# 1-Schematic_CessnaCitationX_PilotBoard.net
KiCad netlist of a schematic drawn in EasyEDA
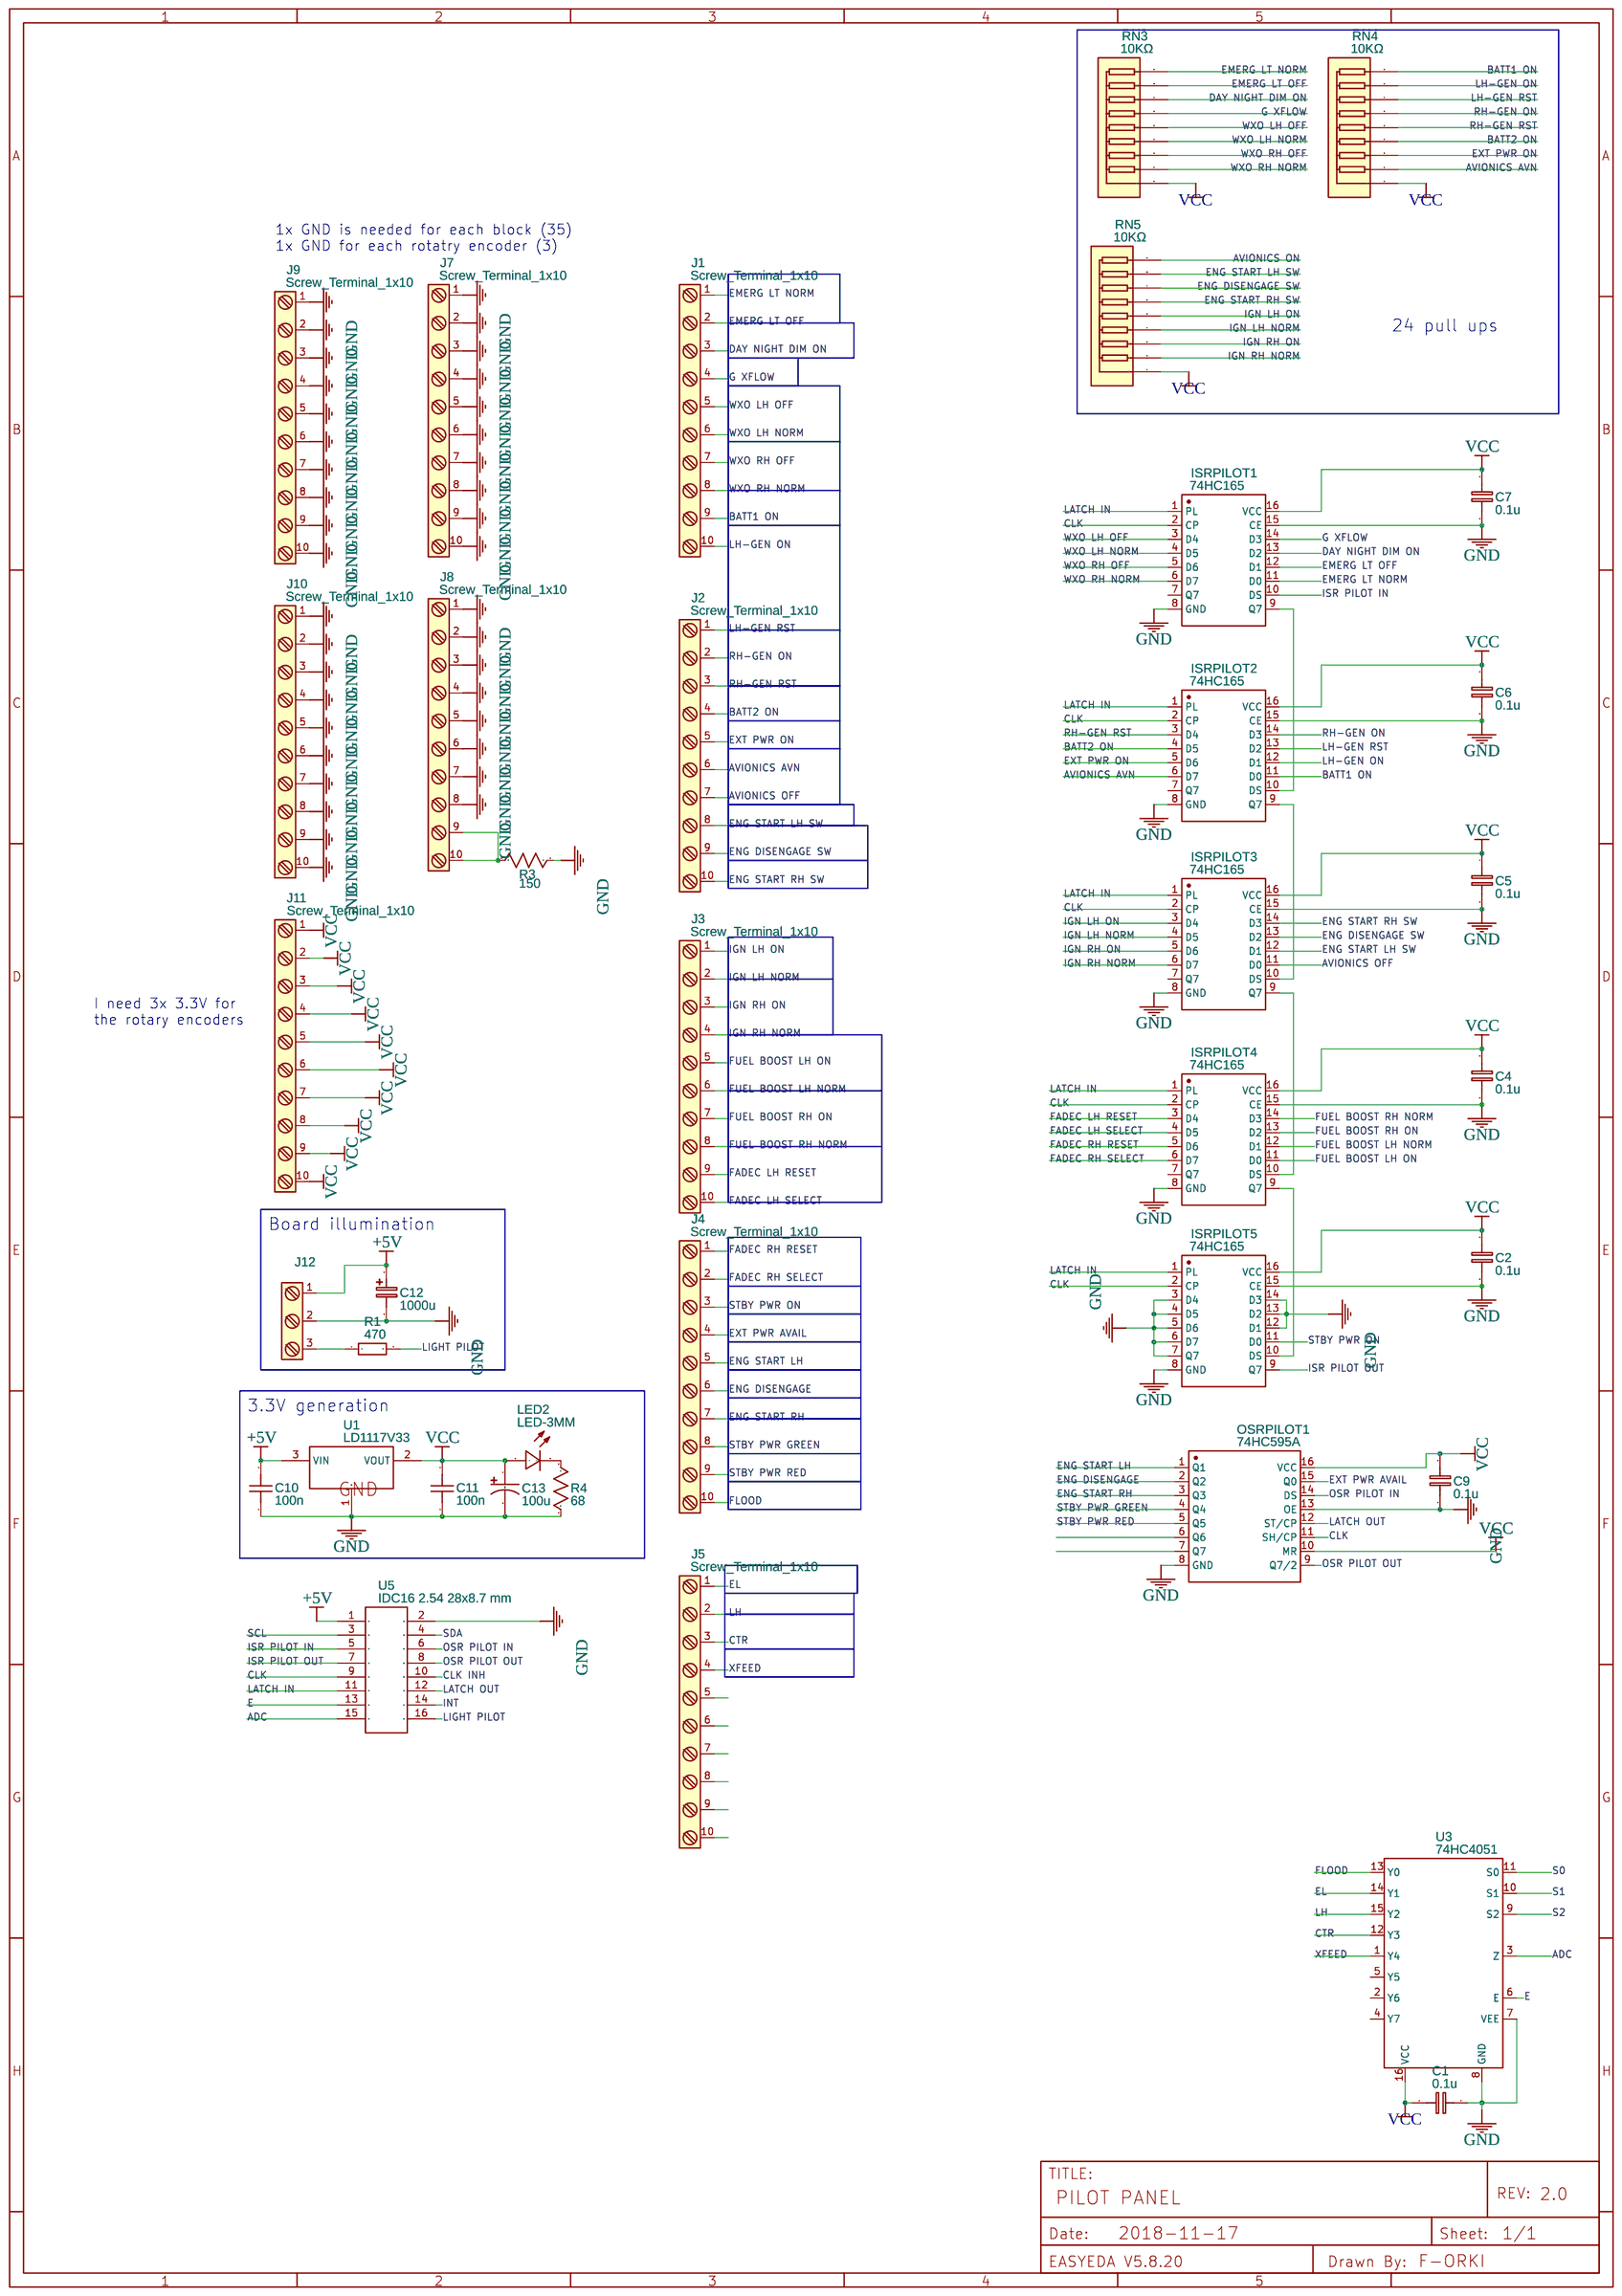
[diagram p0: schematic sheet]

(export (version "E")
  (design (tool "Eeschema 10.0.6"))
  (components
    (comp (ref "C1")
      (value "0.1u")
      (fields (field (name "BOM_Manufacturer Part") "?"))
      (libsource (lib "") (part "Cap_RAD-0.1_EU"))
    )
    (comp (ref "C2")
      (value "0.1u")
      (fields (field (name "BOM_Manufacturer Part") "?"))
      (libsource (lib "") (part "Cap_RAD-0.1_EU_1"))
    )
    (comp (ref "C4")
      (value "0.1u")
      (fields (field (name "BOM_Manufacturer Part") "?"))
      (libsource (lib "") (part "Cap_RAD-0.1_EU_1"))
    )
    (comp (ref "C5")
      (value "0.1u")
      (fields (field (name "BOM_Manufacturer Part") "?"))
      (libsource (lib "") (part "Cap_RAD-0.1_EU_1"))
    )
    (comp (ref "C6")
      (value "0.1u")
      (fields (field (name "BOM_Manufacturer Part") "?"))
      (libsource (lib "") (part "Cap_RAD-0.1_EU_2"))
    )
    (comp (ref "C7")
      (value "0.1u")
      (fields (field (name "BOM_Manufacturer Part") "?"))
      (libsource (lib "") (part "Cap_RAD-0.1_EU_2"))
    )
    (comp (ref "C9")
      (value "0.1u")
      (fields (field (name "BOM_Manufacturer Part") "?"))
      (libsource (lib "") (part "Cap_RAD-0.1_EU_1"))
    )
    (comp (ref "C10")
      (value "100n")
      (fields (field (name "BOM_Manufacturer Part") "?"))
      (libsource (lib "") (part "Cap_RAD-0.1_US"))
    )
    (comp (ref "C11")
      (value "100n")
      (fields (field (name "BOM_Manufacturer Part") "?"))
      (libsource (lib "") (part "Cap_RAD-0.1_US"))
    )
    (comp (ref "C12")
      (value "1000u")
      (fields (field (name "BOM_Manufacturer Part") "?"))
      (libsource (lib "") (part "Cap_Electrolytic(TH)_D3.0XF1.5_EU"))
    )
    (comp (ref "C13")
      (value "100u")
      (fields (field (name "BOM_Manufacturer Part") "?"))
      (libsource (lib "") (part "Cap_Electrolytic(TH)_D3.0XF1.5_US"))
    )
    (comp (ref "ISRPILOT1")
      (value "74HC165")
      (fields
        (field (name "BOM_Manufacturer Part") "74HC165D,653")
        (field (name "BOM_Supplier Part") "C5613")
      )
      (libsource (lib "") (part "Unknown_870_350"))
    )
    (comp (ref "ISRPILOT2")
      (value "74HC165")
      (fields
        (field (name "BOM_Manufacturer Part") "74HC165D,653")
        (field (name "BOM_Supplier Part") "C5613")
      )
      (libsource (lib "") (part "Unknown_870_490"))
    )
    (comp (ref "ISRPILOT3")
      (value "74HC165")
      (fields
        (field (name "BOM_Manufacturer Part") "74HC165D,653")
        (field (name "BOM_Supplier Part") "C5613")
      )
      (libsource (lib "") (part "Unknown_870_625"))
    )
    (comp (ref "ISRPILOT4")
      (value "74HC165")
      (fields
        (field (name "BOM_Manufacturer Part") "74HC165D,653")
        (field (name "BOM_Supplier Part") "C5613")
      )
      (libsource (lib "") (part "Unknown_870_765"))
    )
    (comp (ref "ISRPILOT5")
      (value "74HC165")
      (fields
        (field (name "BOM_Manufacturer Part") "74HC165D,653")
        (field (name "BOM_Supplier Part") "C5613")
      )
      (libsource (lib "") (part "Unknown_870_895"))
    )
    (comp (ref "J1")
      (value "Screw_Terminal_1x10")
      (fields (field (name "BOM_Manufacturer Part") "?"))
      (libsource (lib "") (part "Unknown_495_205"))
    )
    (comp (ref "J2")
      (value "Screw_Terminal_1x10")
      (fields (field (name "BOM_Manufacturer Part") "?"))
      (libsource (lib "") (part "Unknown_495_445"))
    )
    (comp (ref "J3")
      (value "Screw_Terminal_1x10")
      (fields (field (name "BOM_Manufacturer Part") "?"))
      (libsource (lib "") (part "Unknown_495_675"))
    )
    (comp (ref "J4")
      (value "Screw_Terminal_1x10")
      (fields (field (name "BOM_Manufacturer Part") "?"))
      (libsource (lib "") (part "Unknown_495_890"))
    )
    (comp (ref "J5")
      (value "Screw_Terminal_1x10")
      (fields (field (name "BOM_Manufacturer Part") "?"))
      (libsource (lib "") (part "Unknown_495_1130"))
    )
    (comp (ref "J7")
      (value "Screw_Terminal_1x10")
      (fields (field (name "BOM_Manufacturer Part") "?"))
      (libsource (lib "") (part "Unknown_315_205"))
    )
    (comp (ref "J8")
      (value "Screw_Terminal_1x10")
      (fields (field (name "BOM_Manufacturer Part") "?"))
      (libsource (lib "") (part "Unknown_315_430"))
    )
    (comp (ref "J9")
      (value "Screw_Terminal_1x10")
      (fields (field (name "BOM_Manufacturer Part") "?"))
      (libsource (lib "") (part "Unknown_205_210"))
    )
    (comp (ref "J10")
      (value "Screw_Terminal_1x10")
      (fields (field (name "BOM_Manufacturer Part") "?"))
      (libsource (lib "") (part "Unknown_205_435"))
    )
    (comp (ref "J11")
      (value "Screw_Terminal_1x10")
      (fields (field (name "BOM_Manufacturer Part") "?"))
      (libsource (lib "") (part "Unknown_205_750"))
    )
    (comp (ref "J12")
      (value "Screw_Terminal_1x03")
      (fields (field (name "BOM_Manufacturer Part") "?"))
      (libsource (lib "") (part "Unknown_210_940"))
    )
    (comp (ref "LED2")
      (value "LED-3MM")
      (fields
        (field (name "BOM_Manufacturer Part") "204-10SURD/S530-A3")
        (field (name "BOM_Supplier Part") "C99772")
      )
      (libsource (lib "") (part "Unknown_375_1035"))
    )
    (comp (ref "OSRPILOT1")
      (value "74HC595A")
      (fields (field (name "BOM_Supplier Part") "C110383"))
      (libsource (lib "") (part "Unknown_885_1035"))
    )
    (comp (ref "R1")
      (value "470")
      (fields (field (name "BOM_Manufacturer Part") "?"))
      (libsource (lib "") (part "Res_AXIAL-0.3(1/8W)_EU"))
    )
    (comp (ref "R3")
      (value "150")
      (fields (field (name "BOM_Manufacturer Part") "?"))
      (libsource (lib "") (part "Res_AXIAL-0.3(1/8W)_US_1"))
    )
    (comp (ref "R4")
      (value "68")
      (fields (field (name "BOM_Manufacturer Part") "?"))
      (libsource (lib "") (part "Res_AXIAL-0.3(1/8W)_US"))
    )
    (comp (ref "RN3")
      (value "10KΩ")
      (fields (field (name "BOM_Manufacturer Part") "A09-103JP") (field (name "BOM_Supplier Part") "C8692"))
      (libsource (lib "") (part "A09-103JP"))
    )
    (comp (ref "RN4")
      (value "10KΩ")
      (fields (field (name "BOM_Manufacturer Part") "A09-103JP") (field (name "BOM_Supplier Part") "C8692"))
      (libsource (lib "") (part "A09-103JP"))
    )
    (comp (ref "RN5")
      (value "10KΩ")
      (fields (field (name "BOM_Manufacturer Part") "A09-103JP") (field (name "BOM_Supplier Part") "C8692"))
      (libsource (lib "") (part "A09-103JP"))
    )
    (comp (ref "U1")
      (value "LD1117V33")
      (fields (field (name "BOM_Supplier Part") "C283467"))
      (libsource (lib "") (part "Unknown_245_1060"))
    )
    (comp (ref "U3")
      (value "74HC4051")
      (fields (field (name "BOM_Manufacturer Part") "?"))
      (libsource (lib "") (part "Unknown_1030_1395"))
    )
    (comp (ref "U5")
      (value "IDC16 2.54 28x8.7 mm")
      (fields (field (name "BOM_Manufacturer Part") "?"))
      (libsource (lib "") (part "Unknown_235_1235"))
    )
  )
  (nets
    (net (code "1") (name "+5V") (class "Default")
      (node (ref "C10") (pin "2") (pinfunction "2_2") (pintype "unspecified"))
      (node (ref "C12") (pin "1") (pinfunction "1_1") (pintype "unspecified"))
      (node (ref "J12") (pin "1") (pintype "unspecified"))
      (node (ref "U1") (pin "3") (pinfunction "VIN_3") (pintype "passive"))
      (node (ref "U5") (pin "1") (pinfunction "P1_1") (pintype "unspecified"))
    )
    (net (code "2") (name "/ADC") (class "Default")
      (node (ref "U3") (pin "3") (pinfunction "Z_3") (pintype "unspecified"))
      (node (ref "U5") (pin "15") (pinfunction "15_15") (pintype "unspecified"))
    )
    (net (code "3") (name "/AVIONICS AVN") (class "Default")
      (node (ref "ISRPILOT2") (pin "6") (pinfunction "D7_6") (pintype "unspecified"))
      (node (ref "J2") (pin "6") (pintype "unspecified"))
      (node (ref "RN4") (pin "2") (pinfunction "2_2") (pintype "input"))
    )
    (net (code "4") (name "/AVIONICS OFF") (class "Default")
      (node (ref "ISRPILOT3") (pin "11") (pinfunction "D0_11") (pintype "unspecified"))
      (node (ref "J2") (pin "7") (pintype "unspecified"))
    )
    (net (code "5") (name "/AVIONICS ON") (class "Default")
      (node (ref "RN5") (pin "9") (pinfunction "9_9") (pintype "input"))
    )
    (net (code "6") (name "/BATT1 ON") (class "Default")
      (node (ref "ISRPILOT2") (pin "11") (pinfunction "D0_11") (pintype "unspecified"))
      (node (ref "J1") (pin "9") (pintype "unspecified"))
      (node (ref "RN4") (pin "9") (pinfunction "9_9") (pintype "input"))
    )
    (net (code "7") (name "/BATT2 ON") (class "Default")
      (node (ref "ISRPILOT2") (pin "4") (pinfunction "D5_4") (pintype "unspecified"))
      (node (ref "J2") (pin "4") (pintype "unspecified"))
      (node (ref "RN4") (pin "4") (pinfunction "4_4") (pintype "input"))
    )
    (net (code "8") (name "/CLK") (class "Default")
      (node (ref "ISRPILOT1") (pin "2") (pinfunction "CP_2") (pintype "unspecified"))
      (node (ref "ISRPILOT2") (pin "2") (pinfunction "CP_2") (pintype "unspecified"))
      (node (ref "ISRPILOT3") (pin "2") (pinfunction "CP_2") (pintype "unspecified"))
      (node (ref "ISRPILOT4") (pin "2") (pinfunction "CP_2") (pintype "unspecified"))
      (node (ref "ISRPILOT5") (pin "2") (pinfunction "CP_2") (pintype "unspecified"))
      (node (ref "OSRPILOT1") (pin "11") (pinfunction "SH/CP_11") (pintype "unspecified"))
      (node (ref "U5") (pin "9") (pinfunction "P9_9") (pintype "unspecified"))
    )
    (net (code "9") (name "/CLK INH") (class "Default")
      (node (ref "U5") (pin "10") (pinfunction "P10_10") (pintype "unspecified"))
    )
    (net (code "10") (name "/CTR") (class "Default")
      (node (ref "J5") (pin "3") (pintype "unspecified"))
      (node (ref "U3") (pin "12") (pinfunction "Y3_12") (pintype "unspecified"))
    )
    (net (code "11") (name "/DAY NIGHT DIM ON") (class "Default")
      (node (ref "ISRPILOT1") (pin "13") (pinfunction "D2_13") (pintype "unspecified"))
      (node (ref "J1") (pin "3") (pintype "unspecified"))
      (node (ref "RN3") (pin "7") (pinfunction "7_7") (pintype "input"))
    )
    (net (code "12") (name "/E") (class "Default")
      (node (ref "U3") (pin "6") (pinfunction "E_6") (pintype "unspecified"))
      (node (ref "U5") (pin "13") (pinfunction "13_13") (pintype "unspecified"))
    )
    (net (code "13") (name "/EL") (class "Default")
      (node (ref "J5") (pin "1") (pintype "unspecified"))
      (node (ref "U3") (pin "14") (pinfunction "Y1_14") (pintype "unspecified"))
    )
    (net (code "14") (name "/EMERG LT NORM") (class "Default")
      (node (ref "ISRPILOT1") (pin "11") (pinfunction "D0_11") (pintype "unspecified"))
      (node (ref "J1") (pin "1") (pintype "unspecified"))
      (node (ref "RN3") (pin "9") (pinfunction "9_9") (pintype "input"))
    )
    (net (code "15") (name "/EMERG LT OFF") (class "Default")
      (node (ref "ISRPILOT1") (pin "12") (pinfunction "D1_12") (pintype "unspecified"))
      (node (ref "J1") (pin "2") (pintype "unspecified"))
      (node (ref "RN3") (pin "8") (pinfunction "8_8") (pintype "input"))
    )
    (net (code "16") (name "/ENG DISENGAGE") (class "Default")
      (node (ref "J4") (pin "6") (pintype "unspecified"))
      (node (ref "OSRPILOT1") (pin "2") (pinfunction "Q2_2") (pintype "unspecified"))
    )
    (net (code "17") (name "/ENG DISENGAGE SW") (class "Default")
      (node (ref "ISRPILOT3") (pin "13") (pinfunction "D2_13") (pintype "unspecified"))
      (node (ref "J2") (pin "9") (pintype "unspecified"))
      (node (ref "RN5") (pin "7") (pinfunction "7_7") (pintype "input"))
    )
    (net (code "18") (name "/ENG START LH") (class "Default")
      (node (ref "J4") (pin "5") (pintype "unspecified"))
      (node (ref "OSRPILOT1") (pin "1") (pinfunction "Q1_1") (pintype "unspecified"))
    )
    (net (code "19") (name "/ENG START LH SW") (class "Default")
      (node (ref "ISRPILOT3") (pin "12") (pinfunction "D1_12") (pintype "unspecified"))
      (node (ref "J2") (pin "8") (pintype "unspecified"))
      (node (ref "RN5") (pin "8") (pinfunction "8_8") (pintype "input"))
    )
    (net (code "20") (name "/ENG START RH") (class "Default")
      (node (ref "J4") (pin "7") (pintype "unspecified"))
      (node (ref "OSRPILOT1") (pin "3") (pinfunction "Q3_3") (pintype "unspecified"))
    )
    (net (code "21") (name "/ENG START RH SW") (class "Default")
      (node (ref "ISRPILOT3") (pin "14") (pinfunction "D3_14") (pintype "unspecified"))
      (node (ref "J2") (pin "10") (pintype "unspecified"))
      (node (ref "RN5") (pin "6") (pinfunction "6_6") (pintype "input"))
    )
    (net (code "22") (name "/EXT PWR AVAIL") (class "Default")
      (node (ref "J4") (pin "4") (pintype "unspecified"))
      (node (ref "OSRPILOT1") (pin "15") (pinfunction "Q0_15") (pintype "unspecified"))
    )
    (net (code "23") (name "/EXT PWR ON") (class "Default")
      (node (ref "ISRPILOT2") (pin "5") (pinfunction "D6_5") (pintype "unspecified"))
      (node (ref "J2") (pin "5") (pintype "unspecified"))
      (node (ref "RN4") (pin "3") (pinfunction "3_3") (pintype "input"))
    )
    (net (code "24") (name "/FADEC LH RESET") (class "Default")
      (node (ref "ISRPILOT4") (pin "3") (pinfunction "D4_3") (pintype "unspecified"))
      (node (ref "J3") (pin "9") (pintype "unspecified"))
    )
    (net (code "25") (name "/FADEC LH SELECT") (class "Default")
      (node (ref "ISRPILOT4") (pin "4") (pinfunction "D5_4") (pintype "unspecified"))
      (node (ref "J3") (pin "10") (pintype "unspecified"))
    )
    (net (code "26") (name "/FADEC RH RESET") (class "Default")
      (node (ref "ISRPILOT4") (pin "5") (pinfunction "D6_5") (pintype "unspecified"))
      (node (ref "J4") (pin "1") (pintype "unspecified"))
    )
    (net (code "27") (name "/FADEC RH SELECT") (class "Default")
      (node (ref "ISRPILOT4") (pin "6") (pinfunction "D7_6") (pintype "unspecified"))
      (node (ref "J4") (pin "2") (pintype "unspecified"))
    )
    (net (code "28") (name "/FLOOD") (class "Default")
      (node (ref "J4") (pin "10") (pintype "unspecified"))
      (node (ref "U3") (pin "13") (pinfunction "Y0_13") (pintype "unspecified"))
    )
    (net (code "29") (name "/FUEL BOOST LH NORM") (class "Default")
      (node (ref "ISRPILOT4") (pin "12") (pinfunction "D1_12") (pintype "unspecified"))
      (node (ref "J3") (pin "6") (pintype "unspecified"))
    )
    (net (code "30") (name "/FUEL BOOST LH ON") (class "Default")
      (node (ref "ISRPILOT4") (pin "11") (pinfunction "D0_11") (pintype "unspecified"))
      (node (ref "J3") (pin "5") (pintype "unspecified"))
    )
    (net (code "31") (name "/FUEL BOOST RH NORM") (class "Default")
      (node (ref "ISRPILOT4") (pin "14") (pinfunction "D3_14") (pintype "unspecified"))
      (node (ref "J3") (pin "8") (pintype "unspecified"))
    )
    (net (code "32") (name "/FUEL BOOST RH ON") (class "Default")
      (node (ref "ISRPILOT4") (pin "13") (pinfunction "D2_13") (pintype "unspecified"))
      (node (ref "J3") (pin "7") (pintype "unspecified"))
    )
    (net (code "33") (name "/G XFLOW") (class "Default")
      (node (ref "ISRPILOT1") (pin "14") (pinfunction "D3_14") (pintype "unspecified"))
      (node (ref "J1") (pin "4") (pintype "unspecified"))
      (node (ref "RN3") (pin "6") (pinfunction "6_6") (pintype "input"))
    )
    (net (code "34") (name "/IGN LH NORM") (class "Default")
      (node (ref "ISRPILOT3") (pin "4") (pinfunction "D5_4") (pintype "unspecified"))
      (node (ref "J3") (pin "2") (pintype "unspecified"))
      (node (ref "RN5") (pin "4") (pinfunction "4_4") (pintype "input"))
    )
    (net (code "35") (name "/IGN LH ON") (class "Default")
      (node (ref "ISRPILOT3") (pin "3") (pinfunction "D4_3") (pintype "unspecified"))
      (node (ref "J3") (pin "1") (pintype "unspecified"))
      (node (ref "RN5") (pin "5") (pinfunction "5_5") (pintype "input"))
    )
    (net (code "36") (name "/IGN RH NORM") (class "Default")
      (node (ref "ISRPILOT3") (pin "6") (pinfunction "D7_6") (pintype "unspecified"))
      (node (ref "J3") (pin "4") (pintype "unspecified"))
      (node (ref "RN5") (pin "2") (pinfunction "2_2") (pintype "input"))
    )
    (net (code "37") (name "/IGN RH ON") (class "Default")
      (node (ref "ISRPILOT3") (pin "5") (pinfunction "D6_5") (pintype "unspecified"))
      (node (ref "J3") (pin "3") (pintype "unspecified"))
      (node (ref "RN5") (pin "3") (pinfunction "3_3") (pintype "input"))
    )
    (net (code "38") (name "/INT") (class "Default")
      (node (ref "U5") (pin "14") (pinfunction "14_14") (pintype "unspecified"))
    )
    (net (code "39") (name "/ISR PILOT IN") (class "Default")
      (node (ref "ISRPILOT1") (pin "10") (pinfunction "DS_10") (pintype "unspecified"))
      (node (ref "U5") (pin "5") (pinfunction "P5_5") (pintype "unspecified"))
    )
    (net (code "40") (name "/ISR PILOT OUT") (class "Default")
      (node (ref "ISRPILOT5") (pin "9") (pinfunction "Q7_9") (pintype "unspecified"))
      (node (ref "U5") (pin "7") (pinfunction "P7_7") (pintype "unspecified"))
    )
    (net (code "41") (name "/LATCH IN") (class "Default")
      (node (ref "ISRPILOT1") (pin "1") (pinfunction "PL_1") (pintype "unspecified"))
      (node (ref "ISRPILOT2") (pin "1") (pinfunction "PL_1") (pintype "unspecified"))
      (node (ref "ISRPILOT3") (pin "1") (pinfunction "PL_1") (pintype "unspecified"))
      (node (ref "ISRPILOT4") (pin "1") (pinfunction "PL_1") (pintype "unspecified"))
      (node (ref "ISRPILOT5") (pin "1") (pinfunction "PL_1") (pintype "unspecified"))
      (node (ref "U5") (pin "11") (pinfunction "11_11") (pintype "unspecified"))
    )
    (net (code "42") (name "/LATCH OUT") (class "Default")
      (node (ref "OSRPILOT1") (pin "12") (pinfunction "ST/CP_12") (pintype "unspecified"))
      (node (ref "U5") (pin "12") (pinfunction "12_12") (pintype "unspecified"))
    )
    (net (code "43") (name "/LH") (class "Default")
      (node (ref "J5") (pin "2") (pintype "unspecified"))
      (node (ref "U3") (pin "15") (pinfunction "Y2_15") (pintype "unspecified"))
    )
    (net (code "44") (name "/LH-GEN ON") (class "Default")
      (node (ref "ISRPILOT2") (pin "12") (pinfunction "D1_12") (pintype "unspecified"))
      (node (ref "J1") (pin "10") (pintype "unspecified"))
      (node (ref "RN4") (pin "8") (pinfunction "8_8") (pintype "input"))
    )
    (net (code "45") (name "/LH-GEN RST") (class "Default")
      (node (ref "ISRPILOT2") (pin "13") (pinfunction "D2_13") (pintype "unspecified"))
      (node (ref "J2") (pin "1") (pintype "unspecified"))
      (node (ref "RN4") (pin "7") (pinfunction "7_7") (pintype "input"))
    )
    (net (code "46") (name "/LIGHT PILOT") (class "Default")
      (node (ref "R1") (pin "2") (pinfunction "2_2") (pintype "unspecified"))
      (node (ref "U5") (pin "16") (pinfunction "16_16") (pintype "unspecified"))
    )
    (net (code "47") (name "/OSR PILOT IN") (class "Default")
      (node (ref "OSRPILOT1") (pin "14") (pinfunction "DS_14") (pintype "unspecified"))
      (node (ref "U5") (pin "6") (pinfunction "P6_6") (pintype "unspecified"))
    )
    (net (code "48") (name "/OSR PILOT OUT") (class "Default")
      (node (ref "OSRPILOT1") (pin "9") (pinfunction "Q7/2_9") (pintype "unspecified"))
      (node (ref "U5") (pin "8") (pinfunction "P8_8") (pintype "unspecified"))
    )
    (net (code "49") (name "/RH-GEN ON") (class "Default")
      (node (ref "ISRPILOT2") (pin "14") (pinfunction "D3_14") (pintype "unspecified"))
      (node (ref "J2") (pin "2") (pintype "unspecified"))
      (node (ref "RN4") (pin "6") (pinfunction "6_6") (pintype "input"))
    )
    (net (code "50") (name "/RH-GEN RST") (class "Default")
      (node (ref "ISRPILOT2") (pin "3") (pinfunction "D4_3") (pintype "unspecified"))
      (node (ref "J2") (pin "3") (pintype "unspecified"))
      (node (ref "RN4") (pin "5") (pinfunction "5_5") (pintype "input"))
    )
    (net (code "51") (name "/S0") (class "Default")
      (node (ref "U3") (pin "11") (pinfunction "S0_11") (pintype "unspecified"))
    )
    (net (code "52") (name "/S1") (class "Default")
      (node (ref "U3") (pin "10") (pinfunction "S1_10") (pintype "unspecified"))
    )
    (net (code "53") (name "/S2") (class "Default")
      (node (ref "U3") (pin "9") (pinfunction "S2_9") (pintype "unspecified"))
    )
    (net (code "54") (name "/SCL") (class "Default")
      (node (ref "U5") (pin "3") (pinfunction "P3_3") (pintype "unspecified"))
    )
    (net (code "55") (name "/SDA") (class "Default")
      (node (ref "U5") (pin "4") (pinfunction "P4_4") (pintype "unspecified"))
    )
    (net (code "56") (name "/STBY PWR GREEN") (class "Default")
      (node (ref "J4") (pin "8") (pintype "unspecified"))
      (node (ref "OSRPILOT1") (pin "4") (pinfunction "Q4_4") (pintype "unspecified"))
    )
    (net (code "57") (name "/STBY PWR ON") (class "Default")
      (node (ref "ISRPILOT5") (pin "11") (pinfunction "D0_11") (pintype "unspecified"))
      (node (ref "J4") (pin "3") (pintype "unspecified"))
    )
    (net (code "58") (name "/STBY PWR RED") (class "Default")
      (node (ref "J4") (pin "9") (pintype "unspecified"))
      (node (ref "OSRPILOT1") (pin "5") (pinfunction "Q5_5") (pintype "unspecified"))
    )
    (net (code "59") (name "/WXO LH NORM") (class "Default")
      (node (ref "ISRPILOT1") (pin "4") (pinfunction "D5_4") (pintype "unspecified"))
      (node (ref "J1") (pin "6") (pintype "unspecified"))
      (node (ref "RN3") (pin "4") (pinfunction "4_4") (pintype "input"))
    )
    (net (code "60") (name "/WXO LH OFF") (class "Default")
      (node (ref "ISRPILOT1") (pin "3") (pinfunction "D4_3") (pintype "unspecified"))
      (node (ref "J1") (pin "5") (pintype "unspecified"))
      (node (ref "RN3") (pin "5") (pinfunction "5_5") (pintype "input"))
    )
    (net (code "61") (name "/WXO RH NORM") (class "Default")
      (node (ref "ISRPILOT1") (pin "6") (pinfunction "D7_6") (pintype "unspecified"))
      (node (ref "J1") (pin "8") (pintype "unspecified"))
      (node (ref "RN3") (pin "2") (pinfunction "2_2") (pintype "input"))
    )
    (net (code "62") (name "/WXO RH OFF") (class "Default")
      (node (ref "ISRPILOT1") (pin "5") (pinfunction "D6_5") (pintype "unspecified"))
      (node (ref "J1") (pin "7") (pintype "unspecified"))
      (node (ref "RN3") (pin "3") (pinfunction "3_3") (pintype "input"))
    )
    (net (code "63") (name "/XFEED") (class "Default")
      (node (ref "J5") (pin "4") (pintype "unspecified"))
      (node (ref "U3") (pin "1") (pinfunction "Y4_1") (pintype "unspecified"))
    )
    (net (code "64") (name "GND") (class "Default")
      (node (ref "C1") (pin "1") (pinfunction "1_1") (pintype "unspecified"))
      (node (ref "C10") (pin "1") (pinfunction "1_1") (pintype "unspecified"))
      (node (ref "C11") (pin "1") (pinfunction "1_1") (pintype "unspecified"))
      (node (ref "C12") (pin "2") (pinfunction "2_2") (pintype "unspecified"))
      (node (ref "C13") (pin "2") (pinfunction "2_2") (pintype "unspecified"))
      (node (ref "C2") (pin "2") (pinfunction "2_2") (pintype "unspecified"))
      (node (ref "C4") (pin "2") (pinfunction "2_2") (pintype "unspecified"))
      (node (ref "C5") (pin "2") (pinfunction "2_2") (pintype "unspecified"))
      (node (ref "C6") (pin "2") (pinfunction "2_2") (pintype "unspecified"))
      (node (ref "C7") (pin "2") (pinfunction "2_2") (pintype "unspecified"))
      (node (ref "C9") (pin "2") (pinfunction "2_2") (pintype "unspecified"))
      (node (ref "ISRPILOT1") (pin "15") (pinfunction "CE_15") (pintype "unspecified"))
      (node (ref "ISRPILOT1") (pin "8") (pinfunction "GND_8") (pintype "unspecified"))
      (node (ref "ISRPILOT2") (pin "15") (pinfunction "CE_15") (pintype "unspecified"))
      (node (ref "ISRPILOT2") (pin "8") (pinfunction "GND_8") (pintype "unspecified"))
      (node (ref "ISRPILOT3") (pin "15") (pinfunction "CE_15") (pintype "unspecified"))
      (node (ref "ISRPILOT3") (pin "8") (pinfunction "GND_8") (pintype "unspecified"))
      (node (ref "ISRPILOT4") (pin "15") (pinfunction "CE_15") (pintype "unspecified"))
      (node (ref "ISRPILOT4") (pin "8") (pinfunction "GND_8") (pintype "unspecified"))
      (node (ref "ISRPILOT5") (pin "12") (pinfunction "D1_12") (pintype "unspecified"))
      (node (ref "ISRPILOT5") (pin "13") (pinfunction "D2_13") (pintype "unspecified"))
      (node (ref "ISRPILOT5") (pin "14") (pinfunction "D3_14") (pintype "unspecified"))
      (node (ref "ISRPILOT5") (pin "15") (pinfunction "CE_15") (pintype "unspecified"))
      (node (ref "ISRPILOT5") (pin "3") (pinfunction "D4_3") (pintype "unspecified"))
      (node (ref "ISRPILOT5") (pin "4") (pinfunction "D5_4") (pintype "unspecified"))
      (node (ref "ISRPILOT5") (pin "5") (pinfunction "D6_5") (pintype "unspecified"))
      (node (ref "ISRPILOT5") (pin "6") (pinfunction "D7_6") (pintype "unspecified"))
      (node (ref "ISRPILOT5") (pin "7") (pinfunction "Q7_7") (pintype "unspecified"))
      (node (ref "ISRPILOT5") (pin "8") (pinfunction "GND_8") (pintype "unspecified"))
      (node (ref "J10") (pin "1") (pintype "unspecified"))
      (node (ref "J10") (pin "10") (pintype "unspecified"))
      (node (ref "J10") (pin "2") (pintype "unspecified"))
      (node (ref "J10") (pin "3") (pintype "unspecified"))
      (node (ref "J10") (pin "4") (pintype "unspecified"))
      (node (ref "J10") (pin "5") (pintype "unspecified"))
      (node (ref "J10") (pin "6") (pintype "unspecified"))
      (node (ref "J10") (pin "7") (pintype "unspecified"))
      (node (ref "J10") (pin "8") (pintype "unspecified"))
      (node (ref "J10") (pin "9") (pintype "unspecified"))
      (node (ref "J12") (pin "2") (pintype "unspecified"))
      (node (ref "J7") (pin "1") (pintype "unspecified"))
      (node (ref "J7") (pin "10") (pintype "unspecified"))
      (node (ref "J7") (pin "2") (pintype "unspecified"))
      (node (ref "J7") (pin "3") (pintype "unspecified"))
      (node (ref "J7") (pin "4") (pintype "unspecified"))
      (node (ref "J7") (pin "5") (pintype "unspecified"))
      (node (ref "J7") (pin "6") (pintype "unspecified"))
      (node (ref "J7") (pin "7") (pintype "unspecified"))
      (node (ref "J7") (pin "8") (pintype "unspecified"))
      (node (ref "J7") (pin "9") (pintype "unspecified"))
      (node (ref "J8") (pin "1") (pintype "unspecified"))
      (node (ref "J8") (pin "2") (pintype "unspecified"))
      (node (ref "J8") (pin "3") (pintype "unspecified"))
      (node (ref "J8") (pin "4") (pintype "unspecified"))
      (node (ref "J8") (pin "5") (pintype "unspecified"))
      (node (ref "J8") (pin "6") (pintype "unspecified"))
      (node (ref "J8") (pin "7") (pintype "unspecified"))
      (node (ref "J8") (pin "8") (pintype "unspecified"))
      (node (ref "J9") (pin "1") (pintype "unspecified"))
      (node (ref "J9") (pin "10") (pintype "unspecified"))
      (node (ref "J9") (pin "2") (pintype "unspecified"))
      (node (ref "J9") (pin "3") (pintype "unspecified"))
      (node (ref "J9") (pin "4") (pintype "unspecified"))
      (node (ref "J9") (pin "5") (pintype "unspecified"))
      (node (ref "J9") (pin "6") (pintype "unspecified"))
      (node (ref "J9") (pin "7") (pintype "unspecified"))
      (node (ref "J9") (pin "8") (pintype "unspecified"))
      (node (ref "J9") (pin "9") (pintype "unspecified"))
      (node (ref "OSRPILOT1") (pin "13") (pinfunction "OE_13") (pintype "unspecified"))
      (node (ref "OSRPILOT1") (pin "8") (pinfunction "GND_8") (pintype "unspecified"))
      (node (ref "R3") (pin "1") (pinfunction "1_1") (pintype "unspecified"))
      (node (ref "R4") (pin "2") (pinfunction "2_2") (pintype "unspecified"))
      (node (ref "U1") (pin "1") (pinfunction "GND_1") (pintype "unspecified"))
      (node (ref "U3") (pin "7") (pinfunction "VEE_7") (pintype "unspecified"))
      (node (ref "U3") (pin "8") (pinfunction "GND_8") (pintype "unspecified"))
      (node (ref "U5") (pin "2") (pinfunction "P2_2") (pintype "unspecified"))
    )
    (net (code "65") (name "Net-(ISRPILOT2-DS)") (class "Default")
      (node (ref "ISRPILOT1") (pin "9") (pinfunction "Q7_9") (pintype "unspecified"))
      (node (ref "ISRPILOT2") (pin "10") (pinfunction "DS_10") (pintype "unspecified"))
    )
    (net (code "66") (name "Net-(ISRPILOT3-DS)") (class "Default")
      (node (ref "ISRPILOT2") (pin "9") (pinfunction "Q7_9") (pintype "unspecified"))
      (node (ref "ISRPILOT3") (pin "10") (pinfunction "DS_10") (pintype "unspecified"))
    )
    (net (code "67") (name "Net-(ISRPILOT4-DS)") (class "Default")
      (node (ref "ISRPILOT3") (pin "9") (pinfunction "Q7_9") (pintype "unspecified"))
      (node (ref "ISRPILOT4") (pin "10") (pinfunction "DS_10") (pintype "unspecified"))
    )
    (net (code "68") (name "Net-(ISRPILOT5-DS)") (class "Default")
      (node (ref "ISRPILOT4") (pin "9") (pinfunction "Q7_9") (pintype "unspecified"))
      (node (ref "ISRPILOT5") (pin "10") (pinfunction "DS_10") (pintype "unspecified"))
    )
    (net (code "69") (name "Net-(J8-Pad10)") (class "Default")
      (node (ref "J8") (pin "10") (pintype "unspecified"))
      (node (ref "J8") (pin "9") (pintype "unspecified"))
      (node (ref "R3") (pin "2") (pinfunction "2_2") (pintype "unspecified"))
    )
    (net (code "70") (name "Net-(J12-Pad3)") (class "Default")
      (node (ref "J12") (pin "3") (pintype "unspecified"))
      (node (ref "R1") (pin "1") (pinfunction "1_1") (pintype "unspecified"))
    )
    (net (code "71") (name "Net-(LED2--)") (class "Default")
      (node (ref "LED2") (pin "2") (pinfunction "-_2") (pintype "unspecified"))
      (node (ref "R4") (pin "1") (pinfunction "1_1") (pintype "unspecified"))
    )
    (net (code "72") (name "VCC") (class "Default")
      (node (ref "C1") (pin "2") (pinfunction "2_2") (pintype "unspecified"))
      (node (ref "C11") (pin "2") (pinfunction "2_2") (pintype "unspecified"))
      (node (ref "C13") (pin "1") (pinfunction "1_1") (pintype "unspecified"))
      (node (ref "C2") (pin "1") (pinfunction "1_1") (pintype "unspecified"))
      (node (ref "C4") (pin "1") (pinfunction "1_1") (pintype "unspecified"))
      (node (ref "C5") (pin "1") (pinfunction "1_1") (pintype "unspecified"))
      (node (ref "C6") (pin "1") (pinfunction "1_1") (pintype "unspecified"))
      (node (ref "C7") (pin "1") (pinfunction "1_1") (pintype "unspecified"))
      (node (ref "C9") (pin "1") (pinfunction "1_1") (pintype "unspecified"))
      (node (ref "ISRPILOT1") (pin "16") (pinfunction "VCC_16") (pintype "unspecified"))
      (node (ref "ISRPILOT2") (pin "16") (pinfunction "VCC_16") (pintype "unspecified"))
      (node (ref "ISRPILOT3") (pin "16") (pinfunction "VCC_16") (pintype "unspecified"))
      (node (ref "ISRPILOT4") (pin "16") (pinfunction "VCC_16") (pintype "unspecified"))
      (node (ref "ISRPILOT5") (pin "16") (pinfunction "VCC_16") (pintype "unspecified"))
      (node (ref "J11") (pin "1") (pintype "unspecified"))
      (node (ref "J11") (pin "10") (pintype "unspecified"))
      (node (ref "J11") (pin "2") (pintype "unspecified"))
      (node (ref "J11") (pin "3") (pintype "unspecified"))
      (node (ref "J11") (pin "4") (pintype "unspecified"))
      (node (ref "J11") (pin "5") (pintype "unspecified"))
      (node (ref "J11") (pin "6") (pintype "unspecified"))
      (node (ref "J11") (pin "7") (pintype "unspecified"))
      (node (ref "J11") (pin "8") (pintype "unspecified"))
      (node (ref "J11") (pin "9") (pintype "unspecified"))
      (node (ref "LED2") (pin "1") (pinfunction "+_1") (pintype "unspecified"))
      (node (ref "OSRPILOT1") (pin "10") (pinfunction "MR_10") (pintype "unspecified"))
      (node (ref "OSRPILOT1") (pin "16") (pinfunction "VCC_16") (pintype "unspecified"))
      (node (ref "RN3") (pin "1") (pinfunction "1_1") (pintype "input"))
      (node (ref "RN4") (pin "1") (pinfunction "1_1") (pintype "input"))
      (node (ref "RN5") (pin "1") (pinfunction "1_1") (pintype "input"))
      (node (ref "U1") (pin "2") (pinfunction "VOUT_2") (pintype "passive"))
      (node (ref "U3") (pin "16") (pinfunction "VCC_16") (pintype "unspecified"))
    )
    (net (code "73") (name "unconnected-(ISRPILOT1-Q7-Pad7)") (class "Default")
      (node (ref "ISRPILOT1") (pin "7") (pinfunction "Q7_7") (pintype "unspecified"))
    )
    (net (code "74") (name "unconnected-(ISRPILOT2-Q7-Pad7)") (class "Default")
      (node (ref "ISRPILOT2") (pin "7") (pinfunction "Q7_7") (pintype "unspecified"))
    )
    (net (code "75") (name "unconnected-(ISRPILOT3-Q7-Pad7)") (class "Default")
      (node (ref "ISRPILOT3") (pin "7") (pinfunction "Q7_7") (pintype "unspecified"))
    )
    (net (code "76") (name "unconnected-(ISRPILOT4-Q7-Pad7)") (class "Default")
      (node (ref "ISRPILOT4") (pin "7") (pinfunction "Q7_7") (pintype "unspecified"))
    )
    (net (code "77") (name "unconnected-(J5-Pad5)") (class "Default")
      (node (ref "J5") (pin "5") (pintype "unspecified"))
    )
    (net (code "78") (name "unconnected-(J5-Pad6)") (class "Default")
      (node (ref "J5") (pin "6") (pintype "unspecified"))
    )
    (net (code "79") (name "unconnected-(J5-Pad7)") (class "Default")
      (node (ref "J5") (pin "7") (pintype "unspecified"))
    )
    (net (code "80") (name "unconnected-(J5-Pad8)") (class "Default")
      (node (ref "J5") (pin "8") (pintype "unspecified"))
    )
    (net (code "81") (name "unconnected-(J5-Pad9)") (class "Default")
      (node (ref "J5") (pin "9") (pintype "unspecified"))
    )
    (net (code "82") (name "unconnected-(J5-Pad10)") (class "Default")
      (node (ref "J5") (pin "10") (pintype "unspecified"))
    )
    (net (code "83") (name "unconnected-(OSRPILOT1-Q6-Pad6)") (class "Default")
      (node (ref "OSRPILOT1") (pin "6") (pinfunction "Q6_6") (pintype "unspecified"))
    )
    (net (code "84") (name "unconnected-(OSRPILOT1-Q7-Pad7)") (class "Default")
      (node (ref "OSRPILOT1") (pin "7") (pinfunction "Q7_7") (pintype "unspecified"))
    )
    (net (code "85") (name "unconnected-(U3-Y5-Pad5)") (class "Default")
      (node (ref "U3") (pin "5") (pinfunction "Y5_5") (pintype "unspecified"))
    )
    (net (code "86") (name "unconnected-(U3-Y6-Pad2)") (class "Default")
      (node (ref "U3") (pin "2") (pinfunction "Y6_2") (pintype "unspecified"))
    )
    (net (code "87") (name "unconnected-(U3-Y7-Pad4)") (class "Default")
      (node (ref "U3") (pin "4") (pinfunction "Y7_4") (pintype "unspecified"))
    )
  )
)
